# ProPrj_Arduino_Project_2026-04-10.net
KiCad netlist of a schematic drawn in EasyEDA Pro
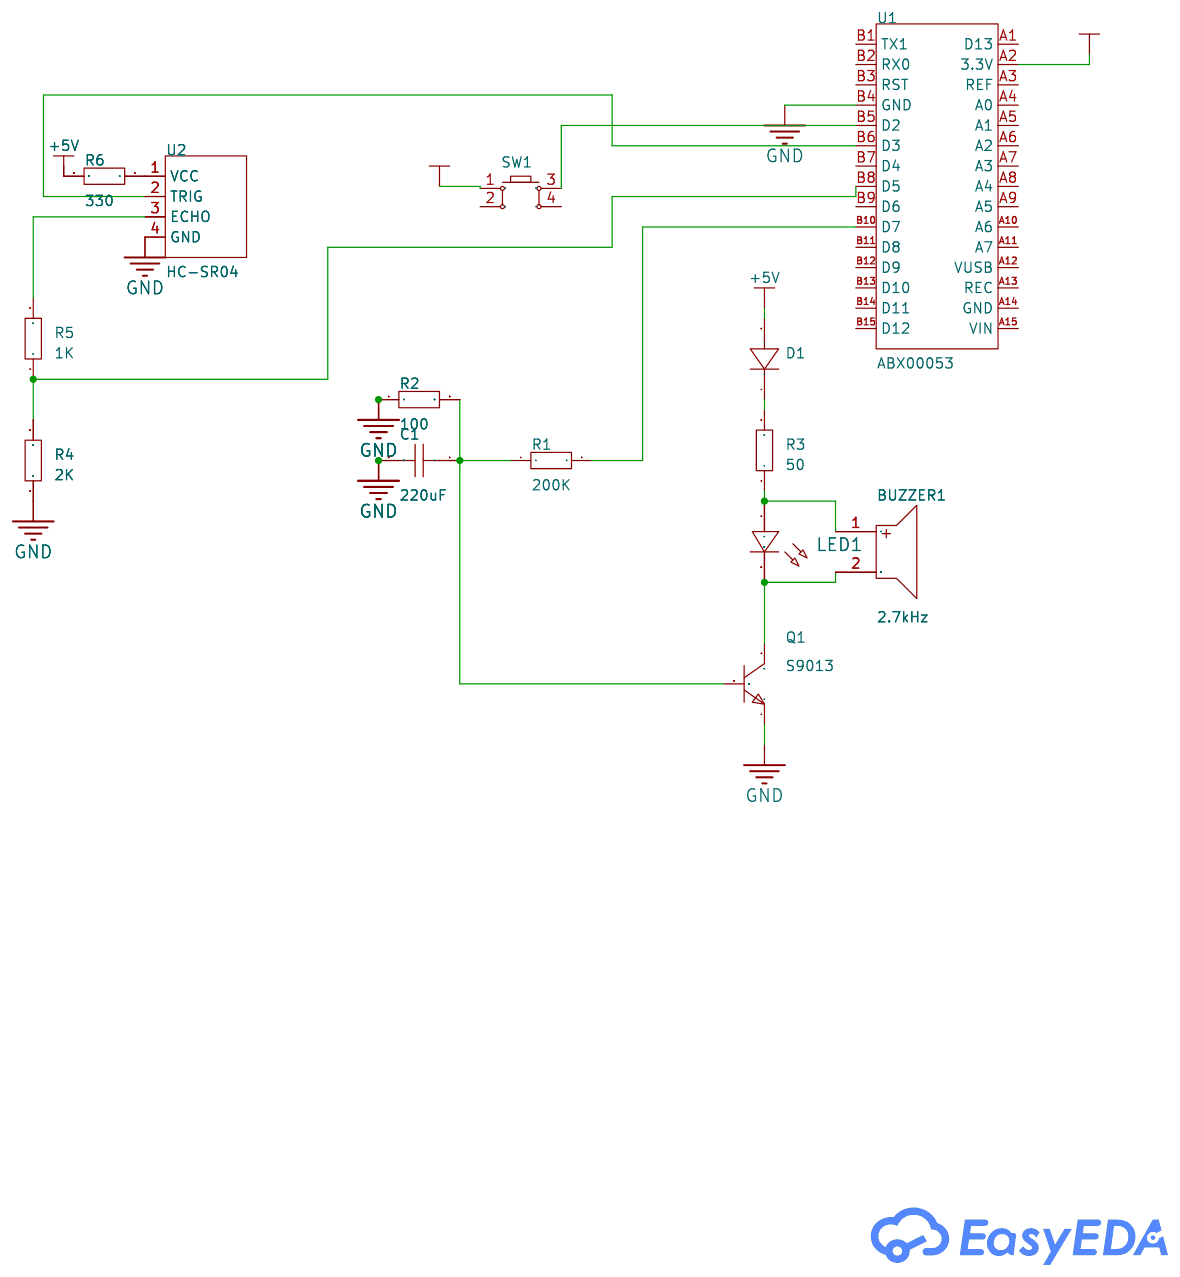
[diagram p0: schematic sheet]

(export (version "E")
  (design (tool "Eeschema 10.0.6"))
  (components
    (comp (ref "BUZZER1")
      (value "2.7kHz")
      (footprint "easyedapro:BUZ-TH_BD9.0-P4.00-D0.6-FD")
      (fields (field (name "Manufacturer Part") "QMB-09B-03") (field (name "Manufacturer") "华能"))
      (libsource (lib "easyedapro") (part "QMB-09B-03"))
    )
    (comp (ref "C1")
      (value "220uF")
      (footprint "easyedapro:C0201")
      (libsource (lib "easyedapro") (part "CAP"))
    )
    (comp (ref "D1")
      (value "~")
      (footprint "easyedapro:DO-41_BD2.4-L4.7-P8.70-D0.9-RD")
      (libsource (lib "easyedapro") (part "D_1N4007"))
    )
    (comp (ref "LED1")
      (value "~")
      (footprint "easyedapro:LED0402-RD_YELLOW")
      (libsource (lib "easyedapro") (part "LED_R"))
    )
    (comp (ref "Q1")
      (value "S9013")
      (footprint "easyedapro:TO-92-3_L4.5-W3.5-P1.27-L")
      (fields (field (name "Manufacturer") "HXY MOSFET(华轩阳电子)"))
      (libsource (lib "easyedapro") (part "S9013_C20616377"))
    )
    (comp (ref "R1")
      (value "200K")
      (footprint "easyedapro:R0603")
      (libsource (lib "easyedapro") (part "Res"))
    )
    (comp (ref "R2") (value "100") (footprint "easyedapro:R0603") (libsource (lib "easyedapro") (part "Res")))
    (comp (ref "R3") (value "50") (footprint "easyedapro:R0603") (libsource (lib "easyedapro") (part "Res")))
    (comp (ref "R4") (value "2K") (footprint "easyedapro:R0603") (libsource (lib "easyedapro") (part "Res")))
    (comp (ref "R5") (value "1K") (footprint "easyedapro:R0603") (libsource (lib "easyedapro") (part "Res")))
    (comp (ref "R6") (value "330") (footprint "easyedapro:R0603") (libsource (lib "easyedapro") (part "Res")))
    (comp (ref "SW1")
      (value "~")
      (footprint "easyedapro:SW-SMD_4P-L6.0-W6.0-P4.50-LS9.0-2")
      (libsource (lib "easyedapro") (part "轻触按键"))
    )
    (comp (ref "U1")
      (value "ABX00053")
      (footprint "easyedapro:COMM-TH_ABX00092")
      (fields (field (name "Manufacturer") "arduino"))
      (libsource (lib "easyedapro") (part "ABX00053"))
    )
    (comp (ref "U2")
      (value "HC-SR04")
      (footprint "easyedapro:TH_HC-SR04V")
      (fields (field (name "Manufacturer") "Universal Microelectronics"))
      (libsource (lib "easyedapro") (part "HC-SR04"))
    )
  )
  (nets
    (net (code "1") (name "+5V") (class "Default")
      (node (ref "D1") (pin "2") (pinfunction "A_2") (pintype "input"))
      (node (ref "R6") (pin "2") (pinfunction "2_2") (pintype "input"))
    )
    (net (code "2") (name "3.3V") (class "Default")
      (node (ref "SW1") (pin "1") (pinfunction "1_1") (pintype "input"))
      (node (ref "U1") (pin "A2") (pinfunction "3.3V_A2") (pintype "unspecified"))
    )
    (net (code "3") (name "GND") (class "Default")
      (node (ref "C1") (pin "2") (pinfunction "2_2") (pintype "input"))
      (node (ref "Q1") (pin "1") (pinfunction "E_1") (pintype "unspecified"))
      (node (ref "R2") (pin "1") (pinfunction "1_1") (pintype "input"))
      (node (ref "R4") (pin "1") (pinfunction "1_1") (pintype "input"))
      (node (ref "U1") (pin "B4") (pinfunction "GND_B4") (pintype "unspecified"))
      (node (ref "U2") (pin "4") (pinfunction "GND_4") (pintype "unspecified"))
    )
    (net (code "4") (name "Net-(D1-K)") (class "Default")
      (node (ref "D1") (pin "1") (pinfunction "K_1") (pintype "input"))
      (node (ref "R3") (pin "2") (pinfunction "2_2") (pintype "input"))
    )
    (net (code "5") (name "Net-(LED1-A)") (class "Default")
      (node (ref "BUZZER1") (pin "1") (pinfunction "1_1") (pintype "unspecified"))
      (node (ref "LED1") (pin "1") (pinfunction "A_1") (pintype "input"))
      (node (ref "R3") (pin "1") (pinfunction "1_1") (pintype "input"))
    )
    (net (code "6") (name "Net-(LED1-C)") (class "Default")
      (node (ref "BUZZER1") (pin "2") (pinfunction "2_2") (pintype "unspecified"))
      (node (ref "LED1") (pin "2") (pinfunction "C_2") (pintype "input"))
      (node (ref "Q1") (pin "3") (pinfunction "C_3") (pintype "unspecified"))
    )
    (net (code "7") (name "Net-(Q1-B)") (class "Default")
      (node (ref "C1") (pin "1") (pinfunction "1_1") (pintype "input"))
      (node (ref "Q1") (pin "2") (pinfunction "B_2") (pintype "unspecified"))
      (node (ref "R1") (pin "1") (pinfunction "1_1") (pintype "input"))
      (node (ref "R2") (pin "2") (pinfunction "2_2") (pintype "input"))
    )
    (net (code "8") (name "Net-(U1-D2)") (class "Default")
      (node (ref "SW1") (pin "3") (pinfunction "3_3") (pintype "input"))
      (node (ref "U1") (pin "B5") (pinfunction "D2_B5") (pintype "unspecified"))
    )
    (net (code "9") (name "Net-(U1-D3)") (class "Default")
      (node (ref "U1") (pin "B6") (pinfunction "D3_B6") (pintype "unspecified"))
      (node (ref "U2") (pin "2") (pinfunction "TRIG_2") (pintype "unspecified"))
    )
    (net (code "10") (name "Net-(U1-D5)") (class "Default")
      (node (ref "R4") (pin "2") (pinfunction "2_2") (pintype "input"))
      (node (ref "R5") (pin "1") (pinfunction "1_1") (pintype "input"))
      (node (ref "U1") (pin "B8") (pinfunction "D5_B8") (pintype "unspecified"))
    )
    (net (code "11") (name "Net-(U1-D7)") (class "Default")
      (node (ref "R1") (pin "2") (pinfunction "2_2") (pintype "input"))
      (node (ref "U1") (pin "B10") (pinfunction "D7_B10") (pintype "unspecified"))
    )
    (net (code "12") (name "Net-(U2-ECHO)") (class "Default")
      (node (ref "R5") (pin "2") (pinfunction "2_2") (pintype "input"))
      (node (ref "U2") (pin "3") (pinfunction "ECHO_3") (pintype "unspecified"))
    )
    (net (code "13") (name "Net-(U2-VCC)") (class "Default")
      (node (ref "R6") (pin "1") (pinfunction "1_1") (pintype "input"))
      (node (ref "U2") (pin "1") (pinfunction "VCC_1") (pintype "unspecified"))
    )
    (net (code "14") (name "unconnected-(SW1-Pad2)") (class "Default")
      (node (ref "SW1") (pin "2") (pinfunction "2_2") (pintype "input"))
    )
    (net (code "15") (name "unconnected-(SW1-Pad4)") (class "Default")
      (node (ref "SW1") (pin "4") (pinfunction "4_4") (pintype "input"))
    )
    (net (code "16") (name "unconnected-(U1-A0-PadA4)") (class "Default")
      (node (ref "U1") (pin "A4") (pinfunction "A0_A4") (pintype "unspecified"))
    )
    (net (code "17") (name "unconnected-(U1-A1-PadA5)") (class "Default")
      (node (ref "U1") (pin "A5") (pinfunction "A1_A5") (pintype "unspecified"))
    )
    (net (code "18") (name "unconnected-(U1-A2-PadA6)") (class "Default")
      (node (ref "U1") (pin "A6") (pinfunction "A2_A6") (pintype "unspecified"))
    )
    (net (code "19") (name "unconnected-(U1-A3-PadA7)") (class "Default")
      (node (ref "U1") (pin "A7") (pinfunction "A3_A7") (pintype "unspecified"))
    )
    (net (code "20") (name "unconnected-(U1-A4-PadA8)") (class "Default")
      (node (ref "U1") (pin "A8") (pinfunction "A4_A8") (pintype "unspecified"))
    )
    (net (code "21") (name "unconnected-(U1-A5-PadA9)") (class "Default")
      (node (ref "U1") (pin "A9") (pinfunction "A5_A9") (pintype "unspecified"))
    )
    (net (code "22") (name "unconnected-(U1-A6-PadA10)") (class "Default")
      (node (ref "U1") (pin "A10") (pinfunction "A6_A10") (pintype "unspecified"))
    )
    (net (code "23") (name "unconnected-(U1-A7-PadA11)") (class "Default")
      (node (ref "U1") (pin "A11") (pinfunction "A7_A11") (pintype "unspecified"))
    )
    (net (code "24") (name "unconnected-(U1-D4-PadB7)") (class "Default")
      (node (ref "U1") (pin "B7") (pinfunction "D4_B7") (pintype "unspecified"))
    )
    (net (code "25") (name "unconnected-(U1-D6-PadB9)") (class "Default")
      (node (ref "U1") (pin "B9") (pinfunction "D6_B9") (pintype "unspecified"))
    )
    (net (code "26") (name "unconnected-(U1-D8-PadB11)") (class "Default")
      (node (ref "U1") (pin "B11") (pinfunction "D8_B11") (pintype "unspecified"))
    )
    (net (code "27") (name "unconnected-(U1-D9-PadB12)") (class "Default")
      (node (ref "U1") (pin "B12") (pinfunction "D9_B12") (pintype "unspecified"))
    )
    (net (code "28") (name "unconnected-(U1-D10-PadB13)") (class "Default")
      (node (ref "U1") (pin "B13") (pinfunction "D10_B13") (pintype "unspecified"))
    )
    (net (code "29") (name "unconnected-(U1-D11-PadB14)") (class "Default")
      (node (ref "U1") (pin "B14") (pinfunction "D11_B14") (pintype "unspecified"))
    )
    (net (code "30") (name "unconnected-(U1-D12-PadB15)") (class "Default")
      (node (ref "U1") (pin "B15") (pinfunction "D12_B15") (pintype "unspecified"))
    )
    (net (code "31") (name "unconnected-(U1-D13-PadA1)") (class "Default")
      (node (ref "U1") (pin "A1") (pinfunction "D13_A1") (pintype "unspecified"))
    )
    (net (code "32") (name "unconnected-(U1-GND-PadA14)") (class "Default")
      (node (ref "U1") (pin "A14") (pinfunction "GND_A14") (pintype "unspecified"))
    )
    (net (code "33") (name "unconnected-(U1-REC-PadA13)") (class "Default")
      (node (ref "U1") (pin "A13") (pinfunction "REC_A13") (pintype "unspecified"))
    )
    (net (code "34") (name "unconnected-(U1-REF-PadA3)") (class "Default")
      (node (ref "U1") (pin "A3") (pinfunction "REF_A3") (pintype "unspecified"))
    )
    (net (code "35") (name "unconnected-(U1-RST-PadB3)") (class "Default")
      (node (ref "U1") (pin "B3") (pinfunction "RST_B3") (pintype "unspecified"))
    )
    (net (code "36") (name "unconnected-(U1-RX0-PadB2)") (class "Default")
      (node (ref "U1") (pin "B2") (pinfunction "RX0_B2") (pintype "unspecified"))
    )
    (net (code "37") (name "unconnected-(U1-TX1-PadB1)") (class "Default")
      (node (ref "U1") (pin "B1") (pinfunction "TX1_B1") (pintype "unspecified"))
    )
    (net (code "38") (name "unconnected-(U1-VIN-PadA15)") (class "Default")
      (node (ref "U1") (pin "A15") (pinfunction "VIN_A15") (pintype "unspecified"))
    )
    (net (code "39") (name "unconnected-(U1-VUSB-PadA12)") (class "Default")
      (node (ref "U1") (pin "A12") (pinfunction "VUSB_A12") (pintype "unspecified"))
    )
  )
)
